# cc.net
KiCad netlist of a schematic drawn in EAGLE
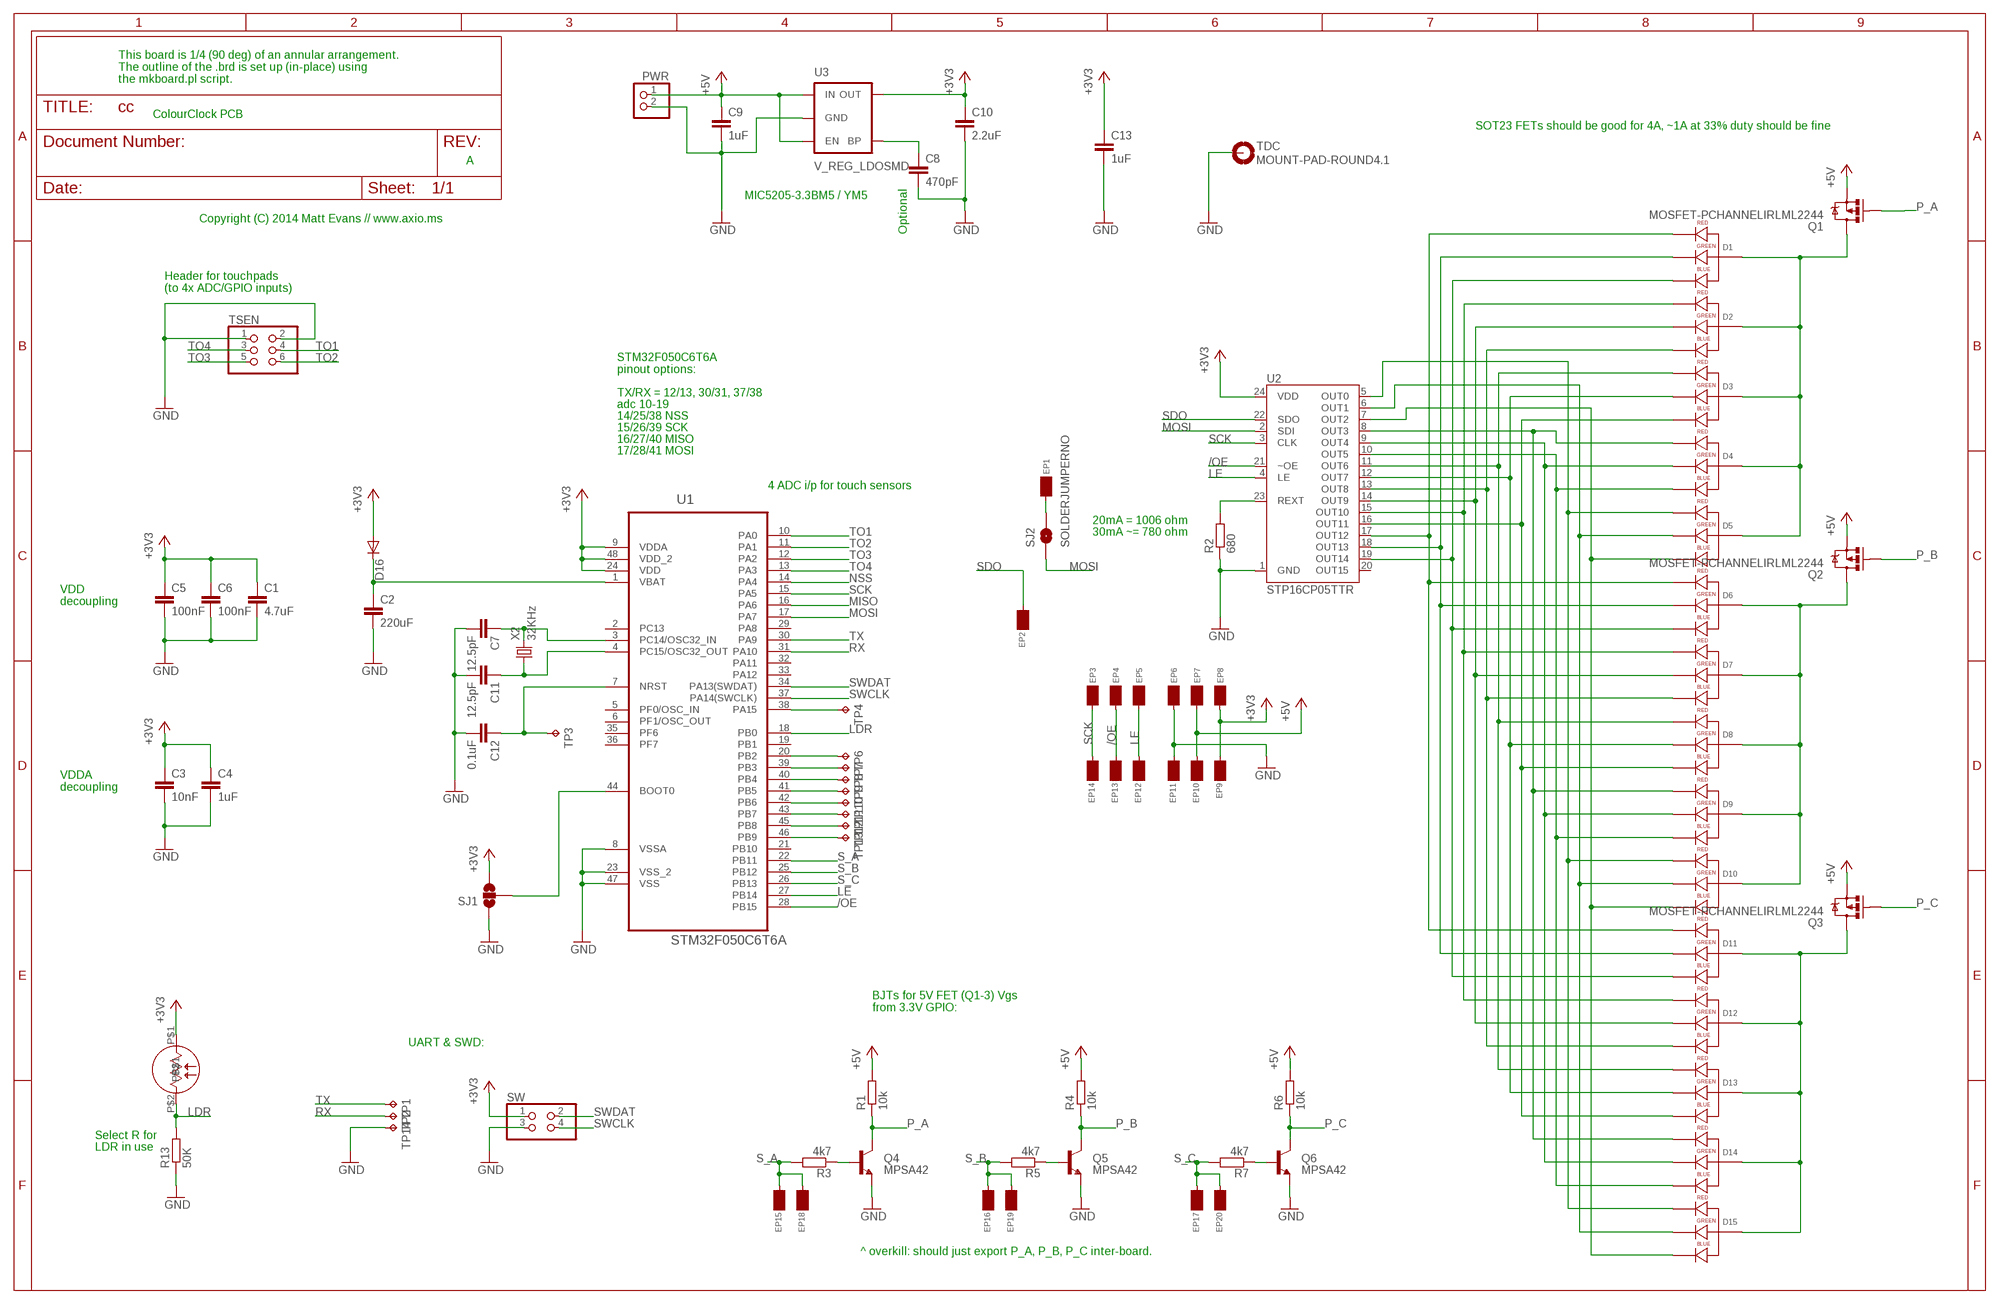
[diagram p0: schematic, sheet 1]

(export (version "E")
  (design (tool "Eeschema 10.0.6"))
  (components
    (comp (ref "C1")
      (value "4.7uF")
      (footprint "eagle-import:C0603")
      (libsource (lib "eagle-import") (part "C-EUC0603"))
    )
    (comp (ref "C2")
      (value "220uF")
      (footprint "eagle-import:C1210K")
      (libsource (lib "eagle-import") (part "C-EUC1210K"))
    )
    (comp (ref "C3")
      (value "10nF")
      (footprint "eagle-import:C0603")
      (libsource (lib "eagle-import") (part "C-EUC0603"))
    )
    (comp (ref "C4")
      (value "1uF")
      (footprint "eagle-import:C0603")
      (libsource (lib "eagle-import") (part "C-EUC0603"))
    )
    (comp (ref "C5")
      (value "100nF")
      (footprint "eagle-import:C0603")
      (libsource (lib "eagle-import") (part "C-EUC0603"))
    )
    (comp (ref "C6")
      (value "100nF")
      (footprint "eagle-import:C0603")
      (libsource (lib "eagle-import") (part "C-EUC0603"))
    )
    (comp (ref "C7")
      (value "12.5pF")
      (footprint "eagle-import:C1005")
      (libsource (lib "eagle-import") (part "C-EUC1005"))
    )
    (comp (ref "C8")
      (value "470pF")
      (footprint "eagle-import:C0603")
      (libsource (lib "eagle-import") (part "C-EUC0603"))
    )
    (comp (ref "C9")
      (value "1uF")
      (footprint "eagle-import:C0603")
      (libsource (lib "eagle-import") (part "C-EUC0603"))
    )
    (comp (ref "C10")
      (value "2.2uF")
      (footprint "eagle-import:C0603")
      (libsource (lib "eagle-import") (part "C-EUC0603"))
    )
    (comp (ref "C11")
      (value "12.5pF")
      (footprint "eagle-import:C1005")
      (libsource (lib "eagle-import") (part "C-EUC1005"))
    )
    (comp (ref "C12")
      (value "0.1uF")
      (footprint "eagle-import:C1005")
      (libsource (lib "eagle-import") (part "C-EUC1005"))
    )
    (comp (ref "C13")
      (value "1uF")
      (footprint "eagle-import:C0603")
      (libsource (lib "eagle-import") (part "C-EUC0603"))
    )
    (comp (ref "D1")
      (value "LED-RGB-CA-THRUDIFFUSE")
      (footprint "eagle-import:LED-RGB-THRU")
      (libsource (lib "eagle-import") (part "LED-RGB-CA-THRUDIFFUSE"))
    )
    (comp (ref "D2")
      (value "LED-RGB-CA-THRUDIFFUSE")
      (footprint "eagle-import:LED-RGB-THRU")
      (libsource (lib "eagle-import") (part "LED-RGB-CA-THRUDIFFUSE"))
    )
    (comp (ref "D3")
      (value "LED-RGB-CA-THRUDIFFUSE")
      (footprint "eagle-import:LED-RGB-THRU")
      (libsource (lib "eagle-import") (part "LED-RGB-CA-THRUDIFFUSE"))
    )
    (comp (ref "D4")
      (value "LED-RGB-CA-THRUDIFFUSE")
      (footprint "eagle-import:LED-RGB-THRU")
      (libsource (lib "eagle-import") (part "LED-RGB-CA-THRUDIFFUSE"))
    )
    (comp (ref "D5")
      (value "LED-RGB-CA-THRUDIFFUSE")
      (footprint "eagle-import:LED-RGB-THRU")
      (libsource (lib "eagle-import") (part "LED-RGB-CA-THRUDIFFUSE"))
    )
    (comp (ref "D6")
      (value "LED-RGB-CA-THRUDIFFUSE")
      (footprint "eagle-import:LED-RGB-THRU")
      (libsource (lib "eagle-import") (part "LED-RGB-CA-THRUDIFFUSE"))
    )
    (comp (ref "D7")
      (value "LED-RGB-CA-THRUDIFFUSE")
      (footprint "eagle-import:LED-RGB-THRU")
      (libsource (lib "eagle-import") (part "LED-RGB-CA-THRUDIFFUSE"))
    )
    (comp (ref "D8")
      (value "LED-RGB-CA-THRUDIFFUSE")
      (footprint "eagle-import:LED-RGB-THRU")
      (libsource (lib "eagle-import") (part "LED-RGB-CA-THRUDIFFUSE"))
    )
    (comp (ref "D9")
      (value "LED-RGB-CA-THRUDIFFUSE")
      (footprint "eagle-import:LED-RGB-THRU")
      (libsource (lib "eagle-import") (part "LED-RGB-CA-THRUDIFFUSE"))
    )
    (comp (ref "D10")
      (value "LED-RGB-CA-THRUDIFFUSE")
      (footprint "eagle-import:LED-RGB-THRU")
      (libsource (lib "eagle-import") (part "LED-RGB-CA-THRUDIFFUSE"))
    )
    (comp (ref "D11")
      (value "LED-RGB-CA-THRUDIFFUSE")
      (footprint "eagle-import:LED-RGB-THRU")
      (libsource (lib "eagle-import") (part "LED-RGB-CA-THRUDIFFUSE"))
    )
    (comp (ref "D12")
      (value "LED-RGB-CA-THRUDIFFUSE")
      (footprint "eagle-import:LED-RGB-THRU")
      (libsource (lib "eagle-import") (part "LED-RGB-CA-THRUDIFFUSE"))
    )
    (comp (ref "D13")
      (value "LED-RGB-CA-THRUDIFFUSE")
      (footprint "eagle-import:LED-RGB-THRU")
      (libsource (lib "eagle-import") (part "LED-RGB-CA-THRUDIFFUSE"))
    )
    (comp (ref "D14")
      (value "LED-RGB-CA-THRUDIFFUSE")
      (footprint "eagle-import:LED-RGB-THRU")
      (libsource (lib "eagle-import") (part "LED-RGB-CA-THRUDIFFUSE"))
    )
    (comp (ref "D15")
      (value "LED-RGB-CA-THRUDIFFUSE")
      (footprint "eagle-import:LED-RGB-THRU")
      (libsource (lib "eagle-import") (part "LED-RGB-CA-THRUDIFFUSE"))
    )
    (comp (ref "D16")
      (value "DIODESOD")
      (footprint "eagle-import:SOD-323")
      (libsource (lib "eagle-import") (part "DIODESOD"))
    )
    (comp (ref "EP1")
      (value "EDGEPAD")
      (footprint "eagle-import:EDGEPAD")
      (libsource (lib "eagle-import") (part "EDGEPAD"))
    )
    (comp (ref "EP2")
      (value "EDGEPAD")
      (footprint "eagle-import:EDGEPAD")
      (libsource (lib "eagle-import") (part "EDGEPAD"))
    )
    (comp (ref "EP3")
      (value "EDGEPAD")
      (footprint "eagle-import:EDGEPAD")
      (libsource (lib "eagle-import") (part "EDGEPAD"))
    )
    (comp (ref "EP4")
      (value "EDGEPAD")
      (footprint "eagle-import:EDGEPAD")
      (libsource (lib "eagle-import") (part "EDGEPAD"))
    )
    (comp (ref "EP5")
      (value "EDGEPAD")
      (footprint "eagle-import:EDGEPAD")
      (libsource (lib "eagle-import") (part "EDGEPAD"))
    )
    (comp (ref "EP6")
      (value "EDGEPAD")
      (footprint "eagle-import:EDGEPAD")
      (libsource (lib "eagle-import") (part "EDGEPAD"))
    )
    (comp (ref "EP7")
      (value "EDGEPAD")
      (footprint "eagle-import:EDGEPAD")
      (libsource (lib "eagle-import") (part "EDGEPAD"))
    )
    (comp (ref "EP8")
      (value "EDGEPAD")
      (footprint "eagle-import:EDGEPAD")
      (libsource (lib "eagle-import") (part "EDGEPAD"))
    )
    (comp (ref "EP9")
      (value "EDGEPAD")
      (footprint "eagle-import:EDGEPAD")
      (libsource (lib "eagle-import") (part "EDGEPAD"))
    )
    (comp (ref "EP10")
      (value "EDGEPAD")
      (footprint "eagle-import:EDGEPAD")
      (libsource (lib "eagle-import") (part "EDGEPAD"))
    )
    (comp (ref "EP11")
      (value "EDGEPAD")
      (footprint "eagle-import:EDGEPAD")
      (libsource (lib "eagle-import") (part "EDGEPAD"))
    )
    (comp (ref "EP12")
      (value "EDGEPAD")
      (footprint "eagle-import:EDGEPAD")
      (libsource (lib "eagle-import") (part "EDGEPAD"))
    )
    (comp (ref "EP13")
      (value "EDGEPAD")
      (footprint "eagle-import:EDGEPAD")
      (libsource (lib "eagle-import") (part "EDGEPAD"))
    )
    (comp (ref "EP14")
      (value "EDGEPAD")
      (footprint "eagle-import:EDGEPAD")
      (libsource (lib "eagle-import") (part "EDGEPAD"))
    )
    (comp (ref "EP15")
      (value "EDGEPAD")
      (footprint "eagle-import:EDGEPAD")
      (libsource (lib "eagle-import") (part "EDGEPAD"))
    )
    (comp (ref "EP16")
      (value "EDGEPAD")
      (footprint "eagle-import:EDGEPAD")
      (libsource (lib "eagle-import") (part "EDGEPAD"))
    )
    (comp (ref "EP17")
      (value "EDGEPAD")
      (footprint "eagle-import:EDGEPAD")
      (libsource (lib "eagle-import") (part "EDGEPAD"))
    )
    (comp (ref "EP18")
      (value "EDGEPAD")
      (footprint "eagle-import:EDGEPAD")
      (libsource (lib "eagle-import") (part "EDGEPAD"))
    )
    (comp (ref "EP19")
      (value "EDGEPAD")
      (footprint "eagle-import:EDGEPAD")
      (libsource (lib "eagle-import") (part "EDGEPAD"))
    )
    (comp (ref "EP20")
      (value "EDGEPAD")
      (footprint "eagle-import:EDGEPAD")
      (libsource (lib "eagle-import") (part "EDGEPAD"))
    )
    (comp (ref "LDR")
      (value "VT935G")
      (footprint "eagle-import:VT935G")
      (libsource (lib "eagle-import") (part "VT935G"))
    )
    (comp (ref "PWR")
      (value "PINHD-1X22MM")
      (footprint "eagle-import:1X02-2MM")
      (libsource (lib "eagle-import") (part "PINHD-1X22MM"))
    )
    (comp (ref "Q1")
      (value "MOSFET-PCHANNELIRLML2244")
      (footprint "eagle-import:SOT23-3")
      (libsource (lib "eagle-import") (part "MOSFET-PCHANNELIRLML2244"))
    )
    (comp (ref "Q2")
      (value "MOSFET-PCHANNELIRLML2244")
      (footprint "eagle-import:SOT23-3")
      (libsource (lib "eagle-import") (part "MOSFET-PCHANNELIRLML2244"))
    )
    (comp (ref "Q3")
      (value "MOSFET-PCHANNELIRLML2244")
      (footprint "eagle-import:SOT23-3")
      (libsource (lib "eagle-import") (part "MOSFET-PCHANNELIRLML2244"))
    )
    (comp (ref "Q4")
      (value "MPSA42")
      (footprint "eagle-import:SOT23-3")
      (libsource (lib "eagle-import") (part "TRANSISTOR_NPNSOT23-3"))
    )
    (comp (ref "Q5")
      (value "MPSA42")
      (footprint "eagle-import:SOT23-3")
      (libsource (lib "eagle-import") (part "TRANSISTOR_NPNSOT23-3"))
    )
    (comp (ref "Q6")
      (value "MPSA42")
      (footprint "eagle-import:SOT23-3")
      (libsource (lib "eagle-import") (part "TRANSISTOR_NPNSOT23-3"))
    )
    (comp (ref "R1")
      (value "10k")
      (footprint "eagle-import:R0603")
      (libsource (lib "eagle-import") (part "R-EU_R0603"))
    )
    (comp (ref "R2")
      (value "680")
      (footprint "eagle-import:R0603")
      (libsource (lib "eagle-import") (part "resistor_R-EU_R0603"))
    )
    (comp (ref "R3")
      (value "4k7")
      (footprint "eagle-import:R0603")
      (libsource (lib "eagle-import") (part "R-EU_R0603"))
    )
    (comp (ref "R4")
      (value "10k")
      (footprint "eagle-import:R0603")
      (libsource (lib "eagle-import") (part "R-EU_R0603"))
    )
    (comp (ref "R5")
      (value "4k7")
      (footprint "eagle-import:R0603")
      (libsource (lib "eagle-import") (part "R-EU_R0603"))
    )
    (comp (ref "R6")
      (value "10k")
      (footprint "eagle-import:R0603")
      (libsource (lib "eagle-import") (part "R-EU_R0603"))
    )
    (comp (ref "R7")
      (value "4k7")
      (footprint "eagle-import:R0603")
      (libsource (lib "eagle-import") (part "R-EU_R0603"))
    )
    (comp (ref "R13")
      (value "50K")
      (footprint "eagle-import:R0603")
      (libsource (lib "eagle-import") (part "R-EU_R0603"))
    )
    (comp (ref "SJ1")
      (value "SOLDERJUMPER_2WAYS")
      (footprint "eagle-import:SJ_3")
      (libsource (lib "eagle-import") (part "SOLDERJUMPER_2WAYS"))
    )
    (comp (ref "SJ2")
      (value "SOLDERJUMPERNO")
      (footprint "eagle-import:SJ_2S-NO")
      (libsource (lib "eagle-import") (part "SOLDERJUMPERNO"))
    )
    (comp (ref "SW")
      (value "PINHD-2X22MM")
      (footprint "eagle-import:2X02-2MM")
      (libsource (lib "eagle-import") (part "PINHD-2X22MM"))
    )
    (comp (ref "TDC")
      (value "MOUNT-PAD-ROUND4.1")
      (footprint "eagle-import:4,1-PAD")
      (libsource (lib "eagle-import") (part "MOUNT-PAD-ROUND4.1"))
    )
    (comp (ref "TP1")
      (value "TPTP06R")
      (footprint "eagle-import:TP06R")
      (libsource (lib "eagle-import") (part "TPTP06R"))
    )
    (comp (ref "TP2")
      (value "TPTP06R")
      (footprint "eagle-import:TP06R")
      (libsource (lib "eagle-import") (part "TPTP06R"))
    )
    (comp (ref "TP3")
      (value "TPTP06R")
      (footprint "eagle-import:TP06R")
      (libsource (lib "eagle-import") (part "TPTP06R"))
    )
    (comp (ref "TP4")
      (value "TPTP06R")
      (footprint "eagle-import:TP06R")
      (libsource (lib "eagle-import") (part "TPTP06R"))
    )
    (comp (ref "TP6")
      (value "TPTP06R")
      (footprint "eagle-import:TP06R")
      (libsource (lib "eagle-import") (part "TPTP06R"))
    )
    (comp (ref "TP7")
      (value "TPTP06R")
      (footprint "eagle-import:TP06R")
      (libsource (lib "eagle-import") (part "TPTP06R"))
    )
    (comp (ref "TP8")
      (value "TPTP06R")
      (footprint "eagle-import:TP06R")
      (libsource (lib "eagle-import") (part "TPTP06R"))
    )
    (comp (ref "TP9")
      (value "TPTP06R")
      (footprint "eagle-import:TP06R")
      (libsource (lib "eagle-import") (part "TPTP06R"))
    )
    (comp (ref "TP10")
      (value "TPTP06R")
      (footprint "eagle-import:TP06R")
      (libsource (lib "eagle-import") (part "TPTP06R"))
    )
    (comp (ref "TP11")
      (value "TPTP06R")
      (footprint "eagle-import:TP06R")
      (libsource (lib "eagle-import") (part "TPTP06R"))
    )
    (comp (ref "TP12")
      (value "TPTP06R")
      (footprint "eagle-import:TP06R")
      (libsource (lib "eagle-import") (part "TPTP06R"))
    )
    (comp (ref "TP13")
      (value "TPTP06R")
      (footprint "eagle-import:TP06R")
      (libsource (lib "eagle-import") (part "TPTP06R"))
    )
    (comp (ref "TP14")
      (value "TPTP06R")
      (footprint "eagle-import:TP06R")
      (libsource (lib "eagle-import") (part "TPTP06R"))
    )
    (comp (ref "TSEN")
      (value "PINHD-2X32MM")
      (footprint "eagle-import:2X03-2MM")
      (libsource (lib "eagle-import") (part "PINHD-2X32MM"))
    )
    (comp (ref "U1")
      (value "STM32F050C6T6A")
      (footprint "eagle-import:QFP50P900X900X160-48N")
      (libsource (lib "eagle-import") (part "STM32F050C6T6A"))
    )
    (comp (ref "U2")
      (value "STP16CP05TTR")
      (footprint "eagle-import:TSSOP24")
      (libsource (lib "eagle-import") (part "STP16CP05TTR"))
    )
    (comp (ref "U3")
      (value "V_REG_LDOSMD")
      (footprint "eagle-import:SOT23-5")
      (libsource (lib "eagle-import") (part "V_REG_LDOSMD"))
    )
    (comp (ref "X2")
      (value "32KHz")
      (footprint "eagle-import:TC26V")
      (libsource (lib "eagle-import") (part "CRYTALTC26V"))
    )
  )
  (nets
    (net (code "1") (name "+3V3") (class "Default")
      (node (ref "C1") (pin "1") (pinfunction "1_1") (pintype "passive"))
      (node (ref "C10") (pin "1") (pinfunction "1_1") (pintype "passive"))
      (node (ref "C13") (pin "1") (pinfunction "1_1") (pintype "passive"))
      (node (ref "C3") (pin "1") (pinfunction "1_1") (pintype "passive"))
      (node (ref "C4") (pin "1") (pinfunction "1_1") (pintype "passive"))
      (node (ref "C5") (pin "1") (pinfunction "1_1") (pintype "passive"))
      (node (ref "C6") (pin "1") (pinfunction "1_1") (pintype "passive"))
      (node (ref "D16") (pin "2") (pinfunction "A_2") (pintype "passive"))
      (node (ref "EP8") (pin "1") (pinfunction "P_1") (pintype "bidirectional"))
      (node (ref "EP9") (pin "1") (pinfunction "P_1") (pintype "bidirectional"))
      (node (ref "LDR") (pin "P$1") (pinfunction "P$1_P$1") (pintype "bidirectional"))
      (node (ref "SJ1") (pin "3") (pinfunction "3_3") (pintype "passive"))
      (node (ref "SW") (pin "1") (pinfunction "1_1") (pintype "passive"))
      (node (ref "U1") (pin "24") (pinfunction "VDD_24") (pintype "power_in"))
      (node (ref "U1") (pin "48") (pinfunction "VDD_2_48") (pintype "power_in"))
      (node (ref "U1") (pin "9") (pinfunction "VDDA_9") (pintype "power_in"))
      (node (ref "U2") (pin "24") (pinfunction "VDD_24") (pintype "bidirectional"))
      (node (ref "U3") (pin "5") (pinfunction "OUT_5") (pintype "passive"))
    )
    (net (code "2") (name "+5V") (class "Default")
      (node (ref "C9") (pin "1") (pinfunction "1_1") (pintype "passive"))
      (node (ref "EP10") (pin "1") (pinfunction "P_1") (pintype "bidirectional"))
      (node (ref "EP7") (pin "1") (pinfunction "P_1") (pintype "bidirectional"))
      (node (ref "PWR") (pin "1") (pinfunction "1_1") (pintype "passive"))
      (node (ref "Q1") (pin "2") (pinfunction "S_2") (pintype "passive"))
      (node (ref "Q2") (pin "2") (pinfunction "S_2") (pintype "passive"))
      (node (ref "Q3") (pin "2") (pinfunction "S_2") (pintype "passive"))
      (node (ref "R1") (pin "2") (pinfunction "2_2") (pintype "passive"))
      (node (ref "R4") (pin "2") (pinfunction "2_2") (pintype "passive"))
      (node (ref "R6") (pin "2") (pinfunction "2_2") (pintype "passive"))
      (node (ref "U3") (pin "1") (pinfunction "IN_1") (pintype "input"))
      (node (ref "U3") (pin "3") (pinfunction "EN_3") (pintype "input"))
    )
    (net (code "3") (name "/LDR") (class "Default")
      (node (ref "LDR") (pin "P$2") (pinfunction "P$2_P$2") (pintype "bidirectional"))
      (node (ref "R13") (pin "2") (pinfunction "2_2") (pintype "passive"))
      (node (ref "U1") (pin "18") (pinfunction "PB0_18") (pintype "bidirectional"))
    )
    (net (code "4") (name "/LE") (class "Default")
      (node (ref "EP12") (pin "1") (pinfunction "P_1") (pintype "bidirectional"))
      (node (ref "EP5") (pin "1") (pinfunction "P_1") (pintype "bidirectional"))
      (node (ref "U1") (pin "27") (pinfunction "PB14_27") (pintype "bidirectional"))
      (node (ref "U2") (pin "4") (pinfunction "LE_4") (pintype "bidirectional"))
    )
    (net (code "5") (name "/MISO") (class "Default")
      (node (ref "U1") (pin "16") (pinfunction "PA6_16") (pintype "bidirectional"))
    )
    (net (code "6") (name "/MOSI") (class "Default")
      (node (ref "SJ2") (pin "1") (pinfunction "1_1") (pintype "passive"))
      (node (ref "U1") (pin "17") (pinfunction "PA7_17") (pintype "bidirectional"))
      (node (ref "U2") (pin "2") (pinfunction "SDI_2") (pintype "bidirectional"))
    )
    (net (code "7") (name "/NSS") (class "Default")
      (node (ref "U1") (pin "14") (pinfunction "PA4_14") (pintype "bidirectional"))
    )
    (net (code "8") (name "/P_A") (class "Default")
      (node (ref "Q1") (pin "1") (pinfunction "G_1") (pintype "passive"))
      (node (ref "Q4") (pin "3") (pinfunction "C_3") (pintype "passive"))
      (node (ref "R1") (pin "1") (pinfunction "1_1") (pintype "passive"))
    )
    (net (code "9") (name "/P_B") (class "Default")
      (node (ref "Q2") (pin "1") (pinfunction "G_1") (pintype "passive"))
      (node (ref "Q5") (pin "3") (pinfunction "C_3") (pintype "passive"))
      (node (ref "R4") (pin "1") (pinfunction "1_1") (pintype "passive"))
    )
    (net (code "10") (name "/P_C") (class "Default")
      (node (ref "Q3") (pin "1") (pinfunction "G_1") (pintype "passive"))
      (node (ref "Q6") (pin "3") (pinfunction "C_3") (pintype "passive"))
      (node (ref "R6") (pin "1") (pinfunction "1_1") (pintype "passive"))
    )
    (net (code "11") (name "/RX") (class "Default")
      (node (ref "TP2") (pin "TP") (pinfunction "TP_TP") (pintype "input"))
      (node (ref "U1") (pin "31") (pinfunction "PA10_31") (pintype "bidirectional"))
    )
    (net (code "12") (name "/SCK") (class "Default")
      (node (ref "EP14") (pin "1") (pinfunction "P_1") (pintype "bidirectional"))
      (node (ref "EP3") (pin "1") (pinfunction "P_1") (pintype "bidirectional"))
      (node (ref "U1") (pin "15") (pinfunction "PA5_15") (pintype "bidirectional"))
      (node (ref "U2") (pin "3") (pinfunction "CLK_3") (pintype "bidirectional"))
    )
    (net (code "13") (name "/SDO") (class "Default")
      (node (ref "EP2") (pin "1") (pinfunction "P_1") (pintype "bidirectional"))
      (node (ref "U2") (pin "22") (pinfunction "SDO_22") (pintype "bidirectional"))
    )
    (net (code "14") (name "/SWCLK") (class "Default")
      (node (ref "SW") (pin "4") (pinfunction "4_4") (pintype "passive"))
      (node (ref "U1") (pin "37") (pinfunction "PA14(SWCLK)_37") (pintype "bidirectional"))
    )
    (net (code "15") (name "/SWDAT") (class "Default")
      (node (ref "SW") (pin "2") (pinfunction "2_2") (pintype "passive"))
      (node (ref "U1") (pin "34") (pinfunction "PA13(SWDAT)_34") (pintype "bidirectional"))
    )
    (net (code "16") (name "/S_A") (class "Default")
      (node (ref "EP15") (pin "1") (pinfunction "P_1") (pintype "bidirectional"))
      (node (ref "EP18") (pin "1") (pinfunction "P_1") (pintype "bidirectional"))
      (node (ref "R3") (pin "2") (pinfunction "2_2") (pintype "passive"))
      (node (ref "U1") (pin "22") (pinfunction "PB11_22") (pintype "bidirectional"))
    )
    (net (code "17") (name "/S_B") (class "Default")
      (node (ref "EP16") (pin "1") (pinfunction "P_1") (pintype "bidirectional"))
      (node (ref "EP19") (pin "1") (pinfunction "P_1") (pintype "bidirectional"))
      (node (ref "R5") (pin "2") (pinfunction "2_2") (pintype "passive"))
      (node (ref "U1") (pin "25") (pinfunction "PB12_25") (pintype "bidirectional"))
    )
    (net (code "18") (name "/S_C") (class "Default")
      (node (ref "EP17") (pin "1") (pinfunction "P_1") (pintype "bidirectional"))
      (node (ref "EP20") (pin "1") (pinfunction "P_1") (pintype "bidirectional"))
      (node (ref "R7") (pin "2") (pinfunction "2_2") (pintype "passive"))
      (node (ref "U1") (pin "26") (pinfunction "PB13_26") (pintype "bidirectional"))
    )
    (net (code "19") (name "/TO1") (class "Default")
      (node (ref "TSEN") (pin "4") (pinfunction "4_4") (pintype "passive"))
      (node (ref "U1") (pin "10") (pinfunction "PA0_10") (pintype "bidirectional"))
    )
    (net (code "20") (name "/TO2") (class "Default")
      (node (ref "TSEN") (pin "6") (pinfunction "6_6") (pintype "passive"))
      (node (ref "U1") (pin "11") (pinfunction "PA1_11") (pintype "bidirectional"))
    )
    (net (code "21") (name "/TO3") (class "Default")
      (node (ref "TSEN") (pin "5") (pinfunction "5_5") (pintype "passive"))
      (node (ref "U1") (pin "12") (pinfunction "PA2_12") (pintype "bidirectional"))
    )
    (net (code "22") (name "/TO4") (class "Default")
      (node (ref "TSEN") (pin "3") (pinfunction "3_3") (pintype "passive"))
      (node (ref "U1") (pin "13") (pinfunction "PA3_13") (pintype "bidirectional"))
    )
    (net (code "23") (name "/TX") (class "Default")
      (node (ref "TP1") (pin "TP") (pinfunction "TP_TP") (pintype "input"))
      (node (ref "U1") (pin "30") (pinfunction "PA9_30") (pintype "bidirectional"))
    )
    (net (code "24") (name "/{slash}OE") (class "Default")
      (node (ref "EP13") (pin "1") (pinfunction "P_1") (pintype "bidirectional"))
      (node (ref "EP4") (pin "1") (pinfunction "P_1") (pintype "bidirectional"))
      (node (ref "U1") (pin "28") (pinfunction "PB15_28") (pintype "bidirectional"))
      (node (ref "U2") (pin "21") (pinfunction "~{OE}_21") (pintype "bidirectional"))
    )
    (net (code "25") (name "GND") (class "Default")
      (node (ref "C1") (pin "2") (pinfunction "2_2") (pintype "passive"))
      (node (ref "C10") (pin "2") (pinfunction "2_2") (pintype "passive"))
      (node (ref "C11") (pin "2") (pinfunction "2_2") (pintype "passive"))
      (node (ref "C12") (pin "2") (pinfunction "2_2") (pintype "passive"))
      (node (ref "C13") (pin "2") (pinfunction "2_2") (pintype "passive"))
      (node (ref "C2") (pin "2") (pinfunction "2_2") (pintype "passive"))
      (node (ref "C3") (pin "2") (pinfunction "2_2") (pintype "passive"))
      (node (ref "C4") (pin "2") (pinfunction "2_2") (pintype "passive"))
      (node (ref "C5") (pin "2") (pinfunction "2_2") (pintype "passive"))
      (node (ref "C6") (pin "2") (pinfunction "2_2") (pintype "passive"))
      (node (ref "C7") (pin "2") (pinfunction "2_2") (pintype "passive"))
      (node (ref "C8") (pin "2") (pinfunction "2_2") (pintype "passive"))
      (node (ref "C9") (pin "2") (pinfunction "2_2") (pintype "passive"))
      (node (ref "EP11") (pin "1") (pinfunction "P_1") (pintype "bidirectional"))
      (node (ref "EP6") (pin "1") (pinfunction "P_1") (pintype "bidirectional"))
      (node (ref "PWR") (pin "2") (pinfunction "2_2") (pintype "passive"))
      (node (ref "Q4") (pin "2") (pinfunction "E_2") (pintype "passive"))
      (node (ref "Q5") (pin "2") (pinfunction "E_2") (pintype "passive"))
      (node (ref "Q6") (pin "2") (pinfunction "E_2") (pintype "passive"))
      (node (ref "R13") (pin "1") (pinfunction "1_1") (pintype "passive"))
      (node (ref "R2") (pin "1") (pinfunction "1_1") (pintype "passive"))
      (node (ref "SJ1") (pin "1") (pinfunction "1_1") (pintype "passive"))
      (node (ref "SW") (pin "3") (pinfunction "3_3") (pintype "passive"))
      (node (ref "TDC") (pin "B4,1") (pinfunction "MOUNT_B4,1") (pintype "passive"))
      (node (ref "TP14") (pin "TP") (pinfunction "TP_TP") (pintype "input"))
      (node (ref "TSEN") (pin "1") (pinfunction "1_1") (pintype "passive"))
      (node (ref "TSEN") (pin "2") (pinfunction "2_2") (pintype "passive"))
      (node (ref "U1") (pin "23") (pinfunction "VSS_2_23") (pintype "passive"))
      (node (ref "U1") (pin "47") (pinfunction "VSS_47") (pintype "passive"))
      (node (ref "U1") (pin "8") (pinfunction "VSSA_8") (pintype "passive"))
      (node (ref "U2") (pin "1") (pinfunction "GND_1") (pintype "bidirectional"))
      (node (ref "U3") (pin "2") (pinfunction "GND_2") (pintype "input"))
    )
    (net (code "26") (name "Net-(D1-ANODE)") (class "Default")
      (node (ref "D1") (pin "2") (pinfunction "ANODE_2") (pintype "bidirectional"))
      (node (ref "D2") (pin "2") (pinfunction "ANODE_2") (pintype "bidirectional"))
      (node (ref "D3") (pin "2") (pinfunction "ANODE_2") (pintype "bidirectional"))
      (node (ref "D4") (pin "2") (pinfunction "ANODE_2") (pintype "bidirectional"))
      (node (ref "D5") (pin "2") (pinfunction "ANODE_2") (pintype "bidirectional"))
      (node (ref "Q1") (pin "3") (pinfunction "D_3") (pintype "passive"))
    )
    (net (code "27") (name "Net-(D1-BLUE_CATHODE)") (class "Default")
      (node (ref "D1") (pin "4") (pinfunction "BLUE_CATHODE_4") (pintype "bidirectional"))
      (node (ref "D11") (pin "4") (pinfunction "BLUE_CATHODE_4") (pintype "bidirectional"))
      (node (ref "D6") (pin "4") (pinfunction "BLUE_CATHODE_4") (pintype "bidirectional"))
      (node (ref "U2") (pin "19") (pinfunction "OUT14_19") (pintype "bidirectional"))
    )
    (net (code "28") (name "Net-(D1-GREEN_CATHODE)") (class "Default")
      (node (ref "D1") (pin "3") (pinfunction "GREEN_CATHODE_3") (pintype "bidirectional"))
      (node (ref "D11") (pin "3") (pinfunction "GREEN_CATHODE_3") (pintype "bidirectional"))
      (node (ref "D6") (pin "3") (pinfunction "GREEN_CATHODE_3") (pintype "bidirectional"))
      (node (ref "U2") (pin "18") (pinfunction "OUT13_18") (pintype "bidirectional"))
    )
    (net (code "29") (name "Net-(D1-RED_CATHODE)") (class "Default")
      (node (ref "D1") (pin "1") (pinfunction "RED_CATHODE_1") (pintype "bidirectional"))
      (node (ref "D11") (pin "1") (pinfunction "RED_CATHODE_1") (pintype "bidirectional"))
      (node (ref "D6") (pin "1") (pinfunction "RED_CATHODE_1") (pintype "bidirectional"))
      (node (ref "U2") (pin "17") (pinfunction "OUT12_17") (pintype "bidirectional"))
    )
    (net (code "30") (name "Net-(D10-ANODE)") (class "Default")
      (node (ref "D10") (pin "2") (pinfunction "ANODE_2") (pintype "bidirectional"))
      (node (ref "D6") (pin "2") (pinfunction "ANODE_2") (pintype "bidirectional"))
      (node (ref "D7") (pin "2") (pinfunction "ANODE_2") (pintype "bidirectional"))
      (node (ref "D8") (pin "2") (pinfunction "ANODE_2") (pintype "bidirectional"))
      (node (ref "D9") (pin "2") (pinfunction "ANODE_2") (pintype "bidirectional"))
      (node (ref "Q2") (pin "3") (pinfunction "D_3") (pintype "passive"))
    )
    (net (code "31") (name "Net-(D10-BLUE_CATHODE)") (class "Default")
      (node (ref "D10") (pin "4") (pinfunction "BLUE_CATHODE_4") (pintype "bidirectional"))
      (node (ref "D15") (pin "4") (pinfunction "BLUE_CATHODE_4") (pintype "bidirectional"))
      (node (ref "D5") (pin "4") (pinfunction "BLUE_CATHODE_4") (pintype "bidirectional"))
      (node (ref "U2") (pin "7") (pinfunction "OUT2_7") (pintype "bidirectional"))
    )
    (net (code "32") (name "Net-(D10-GREEN_CATHODE)") (class "Default")
      (node (ref "D10") (pin "3") (pinfunction "GREEN_CATHODE_3") (pintype "bidirectional"))
      (node (ref "D15") (pin "3") (pinfunction "GREEN_CATHODE_3") (pintype "bidirectional"))
      (node (ref "D5") (pin "3") (pinfunction "GREEN_CATHODE_3") (pintype "bidirectional"))
      (node (ref "U2") (pin "6") (pinfunction "OUT1_6") (pintype "bidirectional"))
    )
    (net (code "33") (name "Net-(D10-RED_CATHODE)") (class "Default")
      (node (ref "D10") (pin "1") (pinfunction "RED_CATHODE_1") (pintype "bidirectional"))
      (node (ref "D15") (pin "1") (pinfunction "RED_CATHODE_1") (pintype "bidirectional"))
      (node (ref "D5") (pin "1") (pinfunction "RED_CATHODE_1") (pintype "bidirectional"))
      (node (ref "U2") (pin "5") (pinfunction "OUT0_5") (pintype "bidirectional"))
    )
    (net (code "34") (name "Net-(D11-ANODE)") (class "Default")
      (node (ref "D11") (pin "2") (pinfunction "ANODE_2") (pintype "bidirectional"))
      (node (ref "D12") (pin "2") (pinfunction "ANODE_2") (pintype "bidirectional"))
      (node (ref "D13") (pin "2") (pinfunction "ANODE_2") (pintype "bidirectional"))
      (node (ref "D14") (pin "2") (pinfunction "ANODE_2") (pintype "bidirectional"))
      (node (ref "D15") (pin "2") (pinfunction "ANODE_2") (pintype "bidirectional"))
      (node (ref "Q3") (pin "3") (pinfunction "D_3") (pintype "passive"))
    )
    (net (code "35") (name "Net-(D12-BLUE_CATHODE)") (class "Default")
      (node (ref "D12") (pin "4") (pinfunction "BLUE_CATHODE_4") (pintype "bidirectional"))
      (node (ref "D2") (pin "4") (pinfunction "BLUE_CATHODE_4") (pintype "bidirectional"))
      (node (ref "D7") (pin "4") (pinfunction "BLUE_CATHODE_4") (pintype "bidirectional"))
      (node (ref "U2") (pin "13") (pinfunction "OUT8_13") (pintype "bidirectional"))
    )
    (net (code "36") (name "Net-(D12-GREEN_CATHODE)") (class "Default")
      (node (ref "D12") (pin "3") (pinfunction "GREEN_CATHODE_3") (pintype "bidirectional"))
      (node (ref "D2") (pin "3") (pinfunction "GREEN_CATHODE_3") (pintype "bidirectional"))
      (node (ref "D7") (pin "3") (pinfunction "GREEN_CATHODE_3") (pintype "bidirectional"))
      (node (ref "U2") (pin "14") (pinfunction "OUT9_14") (pintype "bidirectional"))
    )
    (net (code "37") (name "Net-(D12-RED_CATHODE)") (class "Default")
      (node (ref "D12") (pin "1") (pinfunction "RED_CATHODE_1") (pintype "bidirectional"))
      (node (ref "D2") (pin "1") (pinfunction "RED_CATHODE_1") (pintype "bidirectional"))
      (node (ref "D7") (pin "1") (pinfunction "RED_CATHODE_1") (pintype "bidirectional"))
      (node (ref "U2") (pin "15") (pinfunction "OUT10_15") (pintype "bidirectional"))
    )
    (net (code "38") (name "Net-(D13-BLUE_CATHODE)") (class "Default")
      (node (ref "D13") (pin "4") (pinfunction "BLUE_CATHODE_4") (pintype "bidirectional"))
      (node (ref "D3") (pin "4") (pinfunction "BLUE_CATHODE_4") (pintype "bidirectional"))
      (node (ref "D8") (pin "4") (pinfunction "BLUE_CATHODE_4") (pintype "bidirectional"))
      (node (ref "U2") (pin "16") (pinfunction "OUT11_16") (pintype "bidirectional"))
    )
    (net (code "39") (name "Net-(D13-GREEN_CATHODE)") (class "Default")
      (node (ref "D13") (pin "3") (pinfunction "GREEN_CATHODE_3") (pintype "bidirectional"))
      (node (ref "D3") (pin "3") (pinfunction "GREEN_CATHODE_3") (pintype "bidirectional"))
      (node (ref "D8") (pin "3") (pinfunction "GREEN_CATHODE_3") (pintype "bidirectional"))
      (node (ref "U2") (pin "12") (pinfunction "OUT7_12") (pintype "bidirectional"))
    )
    (net (code "40") (name "Net-(D13-RED_CATHODE)") (class "Default")
      (node (ref "D13") (pin "1") (pinfunction "RED_CATHODE_1") (pintype "bidirectional"))
      (node (ref "D3") (pin "1") (pinfunction "RED_CATHODE_1") (pintype "bidirectional"))
      (node (ref "D8") (pin "1") (pinfunction "RED_CATHODE_1") (pintype "bidirectional"))
      (node (ref "U2") (pin "11") (pinfunction "OUT6_11") (pintype "bidirectional"))
    )
    (net (code "41") (name "Net-(D14-BLUE_CATHODE)") (class "Default")
      (node (ref "D14") (pin "4") (pinfunction "BLUE_CATHODE_4") (pintype "bidirectional"))
      (node (ref "D4") (pin "4") (pinfunction "BLUE_CATHODE_4") (pintype "bidirectional"))
      (node (ref "D9") (pin "4") (pinfunction "BLUE_CATHODE_4") (pintype "bidirectional"))
      (node (ref "U2") (pin "10") (pinfunction "OUT5_10") (pintype "bidirectional"))
    )
    (net (code "42") (name "Net-(D14-GREEN_CATHODE)") (class "Default")
      (node (ref "D14") (pin "3") (pinfunction "GREEN_CATHODE_3") (pintype "bidirectional"))
      (node (ref "D4") (pin "3") (pinfunction "GREEN_CATHODE_3") (pintype "bidirectional"))
      (node (ref "D9") (pin "3") (pinfunction "GREEN_CATHODE_3") (pintype "bidirectional"))
      (node (ref "U2") (pin "9") (pinfunction "OUT4_9") (pintype "bidirectional"))
    )
    (net (code "43") (name "Net-(D14-RED_CATHODE)") (class "Default")
      (node (ref "D14") (pin "1") (pinfunction "RED_CATHODE_1") (pintype "bidirectional"))
      (node (ref "D4") (pin "1") (pinfunction "RED_CATHODE_1") (pintype "bidirectional"))
      (node (ref "D9") (pin "1") (pinfunction "RED_CATHODE_1") (pintype "bidirectional"))
      (node (ref "U2") (pin "8") (pinfunction "OUT3_8") (pintype "bidirectional"))
    )
    (net (code "44") (name "Net-(D16-C)") (class "Default")
      (node (ref "C2") (pin "1") (pinfunction "1_1") (pintype "passive"))
      (node (ref "D16") (pin "1") (pinfunction "C_1") (pintype "passive"))
      (node (ref "U1") (pin "1") (pinfunction "VBAT_1") (pintype "power_in"))
    )
    (net (code "45") (name "Net-(EP1-P)") (class "Default")
      (node (ref "EP1") (pin "1") (pinfunction "P_1") (pintype "bidirectional"))
      (node (ref "SJ2") (pin "2") (pinfunction "2_2") (pintype "passive"))
    )
    (net (code "46") (name "Net-(Q4-B)") (class "Default")
      (node (ref "Q4") (pin "1") (pinfunction "B_1") (pintype "passive"))
      (node (ref "R3") (pin "1") (pinfunction "1_1") (pintype "passive"))
    )
    (net (code "47") (name "Net-(Q5-B)") (class "Default")
      (node (ref "Q5") (pin "1") (pinfunction "B_1") (pintype "passive"))
      (node (ref "R5") (pin "1") (pinfunction "1_1") (pintype "passive"))
    )
    (net (code "48") (name "Net-(Q6-B)") (class "Default")
      (node (ref "Q6") (pin "1") (pinfunction "B_1") (pintype "passive"))
      (node (ref "R7") (pin "1") (pinfunction "1_1") (pintype "passive"))
    )
    (net (code "49") (name "Net-(U1-BOOT0)") (class "Default")
      (node (ref "SJ1") (pin "2") (pinfunction "2_2") (pintype "passive"))
      (node (ref "U1") (pin "44") (pinfunction "BOOT0_44") (pintype "input"))
    )
    (net (code "50") (name "Net-(U1-NRST)") (class "Default")
      (node (ref "C12") (pin "1") (pinfunction "1_1") (pintype "passive"))
      (node (ref "TP3") (pin "TP") (pinfunction "TP_TP") (pintype "input"))
      (node (ref "U1") (pin "7") (pinfunction "NRST_7") (pintype "bidirectional"))
    )
    (net (code "51") (name "Net-(U1-PA15)") (class "Default")
      (node (ref "TP4") (pin "TP") (pinfunction "TP_TP") (pintype "input"))
      (node (ref "U1") (pin "38") (pinfunction "PA15_38") (pintype "bidirectional"))
    )
    (net (code "52") (name "Net-(U1-PB2)") (class "Default")
      (node (ref "TP6") (pin "TP") (pinfunction "TP_TP") (pintype "input"))
      (node (ref "U1") (pin "20") (pinfunction "PB2_20") (pintype "bidirectional"))
    )
    (net (code "53") (name "Net-(U1-PB3)") (class "Default")
      (node (ref "TP7") (pin "TP") (pinfunction "TP_TP") (pintype "input"))
      (node (ref "U1") (pin "39") (pinfunction "PB3_39") (pintype "bidirectional"))
    )
    (net (code "54") (name "Net-(U1-PB4)") (class "Default")
      (node (ref "TP8") (pin "TP") (pinfunction "TP_TP") (pintype "input"))
      (node (ref "U1") (pin "40") (pinfunction "PB4_40") (pintype "bidirectional"))
    )
    (net (code "55") (name "Net-(U1-PB5)") (class "Default")
      (node (ref "TP9") (pin "TP") (pinfunction "TP_TP") (pintype "input"))
      (node (ref "U1") (pin "41") (pinfunction "PB5_41") (pintype "bidirectional"))
    )
    (net (code "56") (name "Net-(U1-PB6)") (class "Default")
      (node (ref "TP10") (pin "TP") (pinfunction "TP_TP") (pintype "input"))
      (node (ref "U1") (pin "42") (pinfunction "PB6_42") (pintype "bidirectional"))
    )
    (net (code "57") (name "Net-(U1-PB7)") (class "Default")
      (node (ref "TP11") (pin "TP") (pinfunction "TP_TP") (pintype "input"))
      (node (ref "U1") (pin "43") (pinfunction "PB7_43") (pintype "bidirectional"))
    )
    (net (code "58") (name "Net-(U1-PB8)") (class "Default")
      (node (ref "TP12") (pin "TP") (pinfunction "TP_TP") (pintype "input"))
      (node (ref "U1") (pin "45") (pinfunction "PB8_45") (pintype "bidirectional"))
    )
    (net (code "59") (name "Net-(U1-PB9)") (class "Default")
      (node (ref "TP13") (pin "TP") (pinfunction "TP_TP") (pintype "input"))
      (node (ref "U1") (pin "46") (pinfunction "PB9_46") (pintype "bidirectional"))
    )
    (net (code "60") (name "Net-(U1-PC14{slash}OSC32_IN)") (class "Default")
      (node (ref "C7") (pin "1") (pinfunction "1_1") (pintype "passive"))
      (node (ref "U1") (pin "3") (pinfunction "PC14/OSC32_IN_3") (pintype "bidirectional"))
      (node (ref "X2") (pin "2") (pinfunction "2_2") (pintype "passive"))
    )
    (net (code "61") (name "Net-(U1-PC15{slash}OSC32_OUT)") (class "Default")
      (node (ref "C11") (pin "1") (pinfunction "1_1") (pintype "passive"))
      (node (ref "U1") (pin "4") (pinfunction "PC15/OSC32_OUT_4") (pintype "bidirectional"))
      (node (ref "X2") (pin "1") (pinfunction "1_1") (pintype "passive"))
    )
    (net (code "62") (name "Net-(U2-REXT)") (class "Default")
      (node (ref "R2") (pin "2") (pinfunction "2_2") (pintype "passive"))
      (node (ref "U2") (pin "23") (pinfunction "REXT_23") (pintype "bidirectional"))
    )
    (net (code "63") (name "Net-(U3-BP)") (class "Default")
      (node (ref "C8") (pin "1") (pinfunction "1_1") (pintype "passive"))
      (node (ref "U3") (pin "4") (pinfunction "BP_4") (pintype "input"))
    )
    (net (code "64") (name "unconnected-(U1-PA8-Pad29)") (class "Default")
      (node (ref "U1") (pin "29") (pinfunction "PA8_29") (pintype "bidirectional"))
    )
    (net (code "65") (name "unconnected-(U1-PA11-Pad32)") (class "Default")
      (node (ref "U1") (pin "32") (pinfunction "PA11_32") (pintype "bidirectional"))
    )
    (net (code "66") (name "unconnected-(U1-PA12-Pad33)") (class "Default")
      (node (ref "U1") (pin "33") (pinfunction "PA12_33") (pintype "bidirectional"))
    )
    (net (code "67") (name "unconnected-(U1-PB1-Pad19)") (class "Default")
      (node (ref "U1") (pin "19") (pinfunction "PB1_19") (pintype "bidirectional"))
    )
    (net (code "68") (name "unconnected-(U1-PB10-Pad21)") (class "Default")
      (node (ref "U1") (pin "21") (pinfunction "PB10_21") (pintype "bidirectional"))
    )
    (net (code "69") (name "unconnected-(U1-PC13-Pad2)") (class "Default")
      (node (ref "U1") (pin "2") (pinfunction "PC13_2") (pintype "bidirectional"))
    )
    (net (code "70") (name "unconnected-(U1-PF0{slash}OSC_IN-Pad5)") (class "Default")
      (node (ref "U1") (pin "5") (pinfunction "PF0/OSC_IN_5") (pintype "bidirectional"))
    )
    (net (code "71") (name "unconnected-(U1-PF1{slash}OSC_OUT-Pad6)") (class "Default")
      (node (ref "U1") (pin "6") (pinfunction "PF1/OSC_OUT_6") (pintype "bidirectional"))
    )
    (net (code "72") (name "unconnected-(U1-PF6-Pad35)") (class "Default")
      (node (ref "U1") (pin "35") (pinfunction "PF6_35") (pintype "bidirectional"))
    )
    (net (code "73") (name "unconnected-(U1-PF7-Pad36)") (class "Default")
      (node (ref "U1") (pin "36") (pinfunction "PF7_36") (pintype "bidirectional"))
    )
    (net (code "74") (name "unconnected-(U2-OUT15-Pad20)") (class "Default")
      (node (ref "U2") (pin "20") (pinfunction "OUT15_20") (pintype "bidirectional"))
    )
  )
)
